# gydrodrive_linearPosSensor.net
KiCad netlist of a schematic drawn in Altium Designer
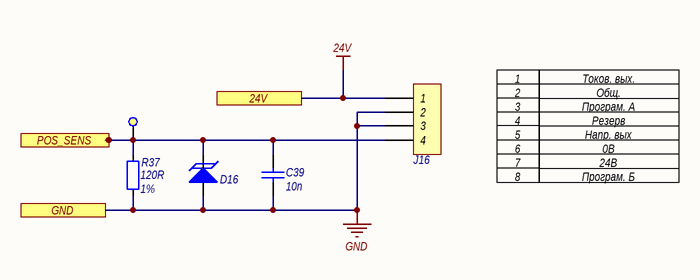
[diagram p0: gydrodrive_linearPosSensor.SchDoc]

(export (version "E")
  (design (tool "Eeschema 10.0.6"))
  (components
    (comp (ref "C39")
      (value "CAP_0805")
      (footprint "CAPC2012-0805M")
      (description "Конденсатор керамический, корпус 0805")
      (fields
        (field (name "CAPACITANCE") "10n")
        (field (name "PART NUMBER") "CAPC_0805")
        (field (name "VOLTAGE") "50V")
      )
      (libsource (lib "StdLib") (part "CAP"))
    )
    (comp (ref "D16")
      (value "SMBJ3V3-E3/52")
      (footprint "SMB_M")
      (description "Защитный диод (TVS)")
      (fields (field (name "VOLTAGE") "3V3"))
      (libsource (lib "StdLib") (part "TVS"))
    )
    (comp (ref "J16")
      (value "DG142V-5.08-04P")
      (footprint "DG142V-5.08-04P")
      (description "Клеммник 4-контактный, шаг 5.08 мм")
      (libsource (lib "StdLib") (part "PIN1x4"))
    )
    (comp (ref "R37")
      (value "RES_0805")
      (footprint "RESC2012-0805M")
      (description "Рез-р, корпус 0805")
      (fields
        (field (name "RESISTANCE") "120R")
        (field (name "PART NUMBER") "RESC_0805")
        (field (name "TOLERANCE") "1%")
      )
      (libsource (lib "StdLib") (part "RES"))
    )
    (comp (ref "TP18")
      (value "Test point 1")
      (footprint "TP_1")
      (description "Тестовый контакт круглый 1 мм")
      (libsource (lib "StdLib") (part "Test point"))
    )
  )
  (nets
    (net (code "1") (name "/POS_SENS") (class "Default")
      (node (ref "C39") (pin "2") (pinfunction "2_2") (pintype "passive"))
      (node (ref "D16") (pin "1") (pinfunction "K_1") (pintype "passive"))
      (node (ref "J16") (pin "4") (pinfunction "4_4") (pintype "passive"))
      (node (ref "R37") (pin "2") (pinfunction "2_2") (pintype "passive"))
      (node (ref "TP18") (pin "1") (pinfunction "1_1") (pintype "passive"))
    )
    (net (code "2") (name "24V") (class "Default")
      (node (ref "J16") (pin "1") (pinfunction "1_1") (pintype "passive"))
    )
    (net (code "3") (name "GND") (class "Default")
      (node (ref "C39") (pin "1") (pinfunction "1_1") (pintype "passive"))
      (node (ref "D16") (pin "2") (pinfunction "A_2") (pintype "passive"))
      (node (ref "J16") (pin "2") (pinfunction "2_2") (pintype "passive"))
      (node (ref "J16") (pin "3") (pinfunction "3_3") (pintype "passive"))
      (node (ref "R37") (pin "1") (pinfunction "1_1") (pintype "passive"))
    )
  )
)
